# circuitPendulumLEDsSmall.net
KiCad netlist of a schematic drawn in EAGLE
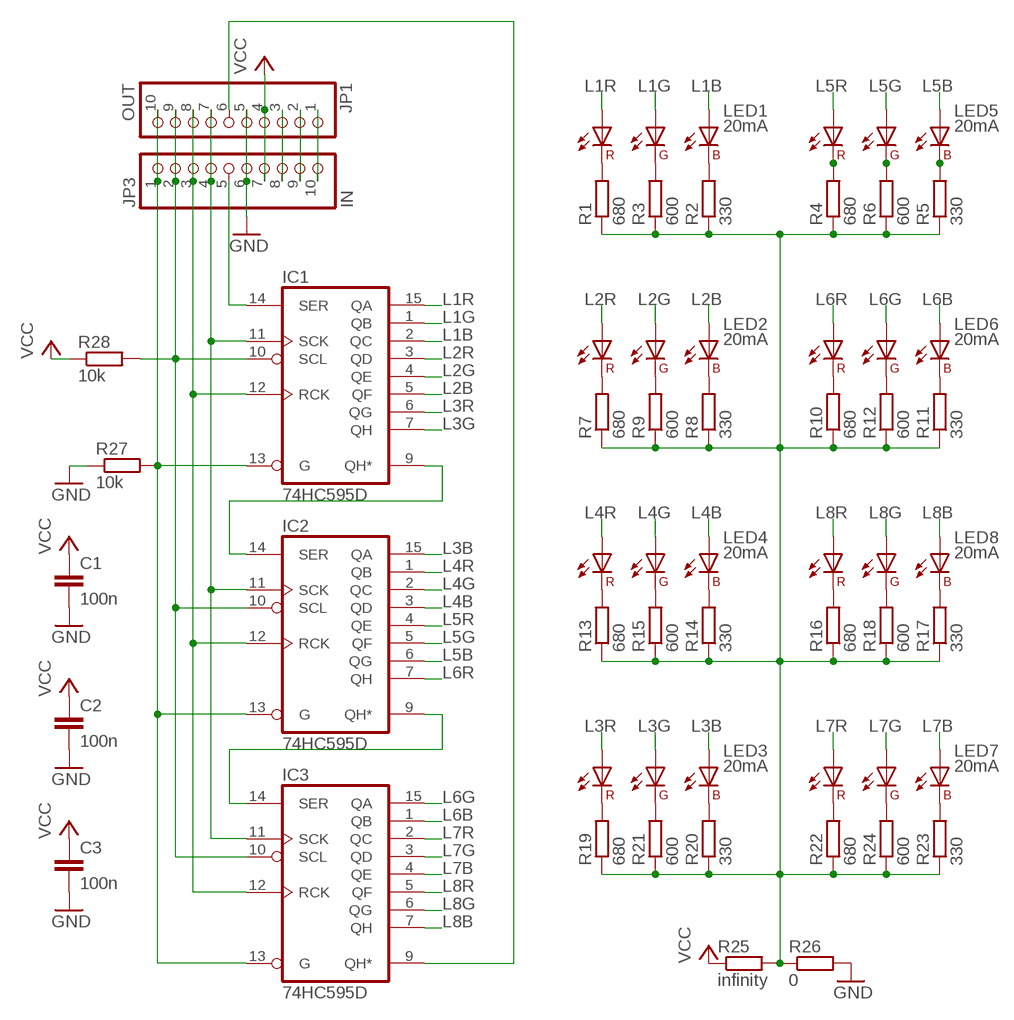
[diagram p0: schematic, sheet 1]

(export (version "E")
  (design (tool "Eeschema 10.0.6"))
  (components
    (comp (ref "C1")
      (value "100n")
      (footprint "eagle-import:C0603")
      (libsource (lib "eagle-import") (part "C-EUC0603"))
    )
    (comp (ref "C2")
      (value "100n")
      (footprint "eagle-import:C0603")
      (libsource (lib "eagle-import") (part "C-EUC0603"))
    )
    (comp (ref "C3")
      (value "100n")
      (footprint "eagle-import:C0603")
      (libsource (lib "eagle-import") (part "C-EUC0603"))
    )
    (comp (ref "IC1")
      (value "74HC595D")
      (footprint "eagle-import:SO16")
      (libsource (lib "eagle-import") (part "74595DHC"))
    )
    (comp (ref "IC2")
      (value "74HC595D")
      (footprint "eagle-import:SO16")
      (libsource (lib "eagle-import") (part "74595DHC"))
    )
    (comp (ref "IC3")
      (value "74HC595D")
      (footprint "eagle-import:SO16")
      (libsource (lib "eagle-import") (part "74595DHC"))
    )
    (comp (ref "JP1")
      (value "OUT")
      (footprint "eagle-import:1X10SMD_90")
      (libsource (lib "eagle-import") (part "PINHD-1X10_2.54-SMD-90°"))
    )
    (comp (ref "JP3")
      (value "IN")
      (footprint "eagle-import:1X10SMD_90")
      (libsource (lib "eagle-import") (part "PINHD-1X10_2.54-SMD-90°"))
    )
    (comp (ref "LED1")
      (value "20mA")
      (footprint "eagle-import:PLCC-6_SAMSUNG")
      (libsource (lib "eagle-import") (part "PLCC-6-RGB-SAMSUNG"))
    )
    (comp (ref "LED2")
      (value "20mA")
      (footprint "eagle-import:PLCC-6_SAMSUNG")
      (libsource (lib "eagle-import") (part "PLCC-6-RGB-SAMSUNG"))
    )
    (comp (ref "LED3")
      (value "20mA")
      (footprint "eagle-import:PLCC-6_SAMSUNG")
      (libsource (lib "eagle-import") (part "PLCC-6-RGB-SAMSUNG"))
    )
    (comp (ref "LED4")
      (value "20mA")
      (footprint "eagle-import:PLCC-6_SAMSUNG")
      (libsource (lib "eagle-import") (part "PLCC-6-RGB-SAMSUNG"))
    )
    (comp (ref "LED5")
      (value "20mA")
      (footprint "eagle-import:PLCC-6_SAMSUNG")
      (libsource (lib "eagle-import") (part "PLCC-6-RGB-SAMSUNG"))
    )
    (comp (ref "LED6")
      (value "20mA")
      (footprint "eagle-import:PLCC-6_SAMSUNG")
      (libsource (lib "eagle-import") (part "PLCC-6-RGB-SAMSUNG"))
    )
    (comp (ref "LED7")
      (value "20mA")
      (footprint "eagle-import:PLCC-6_SAMSUNG")
      (libsource (lib "eagle-import") (part "PLCC-6-RGB-SAMSUNG"))
    )
    (comp (ref "LED8")
      (value "20mA")
      (footprint "eagle-import:PLCC-6_SAMSUNG")
      (libsource (lib "eagle-import") (part "PLCC-6-RGB-SAMSUNG"))
    )
    (comp (ref "R1")
      (value "680")
      (footprint "eagle-import:R0603")
      (libsource (lib "eagle-import") (part "R-EU_R0603"))
    )
    (comp (ref "R2")
      (value "330")
      (footprint "eagle-import:R0603")
      (libsource (lib "eagle-import") (part "R-EU_R0603"))
    )
    (comp (ref "R3")
      (value "600")
      (footprint "eagle-import:R0603")
      (libsource (lib "eagle-import") (part "R-EU_R0603"))
    )
    (comp (ref "R4")
      (value "680")
      (footprint "eagle-import:R0603")
      (libsource (lib "eagle-import") (part "R-EU_R0603"))
    )
    (comp (ref "R5")
      (value "330")
      (footprint "eagle-import:R0603")
      (libsource (lib "eagle-import") (part "R-EU_R0603"))
    )
    (comp (ref "R6")
      (value "600")
      (footprint "eagle-import:R0603")
      (libsource (lib "eagle-import") (part "R-EU_R0603"))
    )
    (comp (ref "R7")
      (value "680")
      (footprint "eagle-import:R0603")
      (libsource (lib "eagle-import") (part "R-EU_R0603"))
    )
    (comp (ref "R8")
      (value "330")
      (footprint "eagle-import:R0603")
      (libsource (lib "eagle-import") (part "R-EU_R0603"))
    )
    (comp (ref "R9")
      (value "600")
      (footprint "eagle-import:R0603")
      (libsource (lib "eagle-import") (part "R-EU_R0603"))
    )
    (comp (ref "R10")
      (value "680")
      (footprint "eagle-import:R0603")
      (libsource (lib "eagle-import") (part "R-EU_R0603"))
    )
    (comp (ref "R11")
      (value "330")
      (footprint "eagle-import:R0603")
      (libsource (lib "eagle-import") (part "R-EU_R0603"))
    )
    (comp (ref "R12")
      (value "600")
      (footprint "eagle-import:R0603")
      (libsource (lib "eagle-import") (part "R-EU_R0603"))
    )
    (comp (ref "R13")
      (value "680")
      (footprint "eagle-import:R0603")
      (libsource (lib "eagle-import") (part "R-EU_R0603"))
    )
    (comp (ref "R14")
      (value "330")
      (footprint "eagle-import:R0603")
      (libsource (lib "eagle-import") (part "R-EU_R0603"))
    )
    (comp (ref "R15")
      (value "600")
      (footprint "eagle-import:R0603")
      (libsource (lib "eagle-import") (part "R-EU_R0603"))
    )
    (comp (ref "R16")
      (value "680")
      (footprint "eagle-import:R0603")
      (libsource (lib "eagle-import") (part "R-EU_R0603"))
    )
    (comp (ref "R17")
      (value "330")
      (footprint "eagle-import:R0603")
      (libsource (lib "eagle-import") (part "R-EU_R0603"))
    )
    (comp (ref "R18")
      (value "600")
      (footprint "eagle-import:R0603")
      (libsource (lib "eagle-import") (part "R-EU_R0603"))
    )
    (comp (ref "R19")
      (value "680")
      (footprint "eagle-import:R0603")
      (libsource (lib "eagle-import") (part "R-EU_R0603"))
    )
    (comp (ref "R20")
      (value "330")
      (footprint "eagle-import:R0603")
      (libsource (lib "eagle-import") (part "R-EU_R0603"))
    )
    (comp (ref "R21")
      (value "600")
      (footprint "eagle-import:R0603")
      (libsource (lib "eagle-import") (part "R-EU_R0603"))
    )
    (comp (ref "R22")
      (value "680")
      (footprint "eagle-import:R0603")
      (libsource (lib "eagle-import") (part "R-EU_R0603"))
    )
    (comp (ref "R23")
      (value "330")
      (footprint "eagle-import:R0603")
      (libsource (lib "eagle-import") (part "R-EU_R0603"))
    )
    (comp (ref "R24")
      (value "600")
      (footprint "eagle-import:R0603")
      (libsource (lib "eagle-import") (part "R-EU_R0603"))
    )
    (comp (ref "R25")
      (value "infinity")
      (footprint "eagle-import:R0603")
      (libsource (lib "eagle-import") (part "R-EU_R0603"))
    )
    (comp (ref "R26")
      (value "0")
      (footprint "eagle-import:R0603")
      (libsource (lib "eagle-import") (part "R-EU_R0603"))
    )
    (comp (ref "R27")
      (value "10k")
      (footprint "eagle-import:R0603")
      (libsource (lib "eagle-import") (part "R-EU_R0603"))
    )
    (comp (ref "R28")
      (value "10k")
      (footprint "eagle-import:R0603")
      (libsource (lib "eagle-import") (part "R-EU_R0603"))
    )
  )
  (nets
    (net (code "1") (name "/L1B") (class "Default")
      (node (ref "IC1") (pin "2") (pinfunction "QC_2") (pintype "tri_state"))
      (node (ref "LED1") (pin "3") (pinfunction "AB_3") (pintype "passive"))
    )
    (net (code "2") (name "/L1G") (class "Default")
      (node (ref "IC1") (pin "1") (pinfunction "QB_1") (pintype "tri_state"))
      (node (ref "LED1") (pin "2") (pinfunction "AG_2") (pintype "passive"))
    )
    (net (code "3") (name "/L1R") (class "Default")
      (node (ref "IC1") (pin "15") (pinfunction "QA_15") (pintype "tri_state"))
      (node (ref "LED1") (pin "1") (pinfunction "AR_1") (pintype "passive"))
    )
    (net (code "4") (name "/L2B") (class "Default")
      (node (ref "IC1") (pin "5") (pinfunction "QF_5") (pintype "tri_state"))
      (node (ref "LED2") (pin "3") (pinfunction "AB_3") (pintype "passive"))
    )
    (net (code "5") (name "/L2G") (class "Default")
      (node (ref "IC1") (pin "4") (pinfunction "QE_4") (pintype "tri_state"))
      (node (ref "LED2") (pin "2") (pinfunction "AG_2") (pintype "passive"))
    )
    (net (code "6") (name "/L2R") (class "Default")
      (node (ref "IC1") (pin "3") (pinfunction "QD_3") (pintype "tri_state"))
      (node (ref "LED2") (pin "1") (pinfunction "AR_1") (pintype "passive"))
    )
    (net (code "7") (name "/L3B") (class "Default")
      (node (ref "IC2") (pin "15") (pinfunction "QA_15") (pintype "tri_state"))
      (node (ref "LED3") (pin "3") (pinfunction "AB_3") (pintype "passive"))
    )
    (net (code "8") (name "/L3G") (class "Default")
      (node (ref "IC1") (pin "7") (pinfunction "QH_7") (pintype "tri_state"))
      (node (ref "LED3") (pin "2") (pinfunction "AG_2") (pintype "passive"))
    )
    (net (code "9") (name "/L3R") (class "Default")
      (node (ref "IC1") (pin "6") (pinfunction "QG_6") (pintype "tri_state"))
      (node (ref "LED3") (pin "1") (pinfunction "AR_1") (pintype "passive"))
    )
    (net (code "10") (name "/L4B") (class "Default")
      (node (ref "IC2") (pin "3") (pinfunction "QD_3") (pintype "tri_state"))
      (node (ref "LED4") (pin "3") (pinfunction "AB_3") (pintype "passive"))
    )
    (net (code "11") (name "/L4G") (class "Default")
      (node (ref "IC2") (pin "2") (pinfunction "QC_2") (pintype "tri_state"))
      (node (ref "LED4") (pin "2") (pinfunction "AG_2") (pintype "passive"))
    )
    (net (code "12") (name "/L4R") (class "Default")
      (node (ref "IC2") (pin "1") (pinfunction "QB_1") (pintype "tri_state"))
      (node (ref "LED4") (pin "1") (pinfunction "AR_1") (pintype "passive"))
    )
    (net (code "13") (name "/L5B") (class "Default")
      (node (ref "IC2") (pin "6") (pinfunction "QG_6") (pintype "tri_state"))
      (node (ref "LED5") (pin "3") (pinfunction "AB_3") (pintype "passive"))
    )
    (net (code "14") (name "/L5G") (class "Default")
      (node (ref "IC2") (pin "5") (pinfunction "QF_5") (pintype "tri_state"))
      (node (ref "LED5") (pin "2") (pinfunction "AG_2") (pintype "passive"))
    )
    (net (code "15") (name "/L5R") (class "Default")
      (node (ref "IC2") (pin "4") (pinfunction "QE_4") (pintype "tri_state"))
      (node (ref "LED5") (pin "1") (pinfunction "AR_1") (pintype "passive"))
    )
    (net (code "16") (name "/L6B") (class "Default")
      (node (ref "IC3") (pin "1") (pinfunction "QB_1") (pintype "tri_state"))
      (node (ref "LED6") (pin "3") (pinfunction "AB_3") (pintype "passive"))
    )
    (net (code "17") (name "/L6G") (class "Default")
      (node (ref "IC3") (pin "15") (pinfunction "QA_15") (pintype "tri_state"))
      (node (ref "LED6") (pin "2") (pinfunction "AG_2") (pintype "passive"))
    )
    (net (code "18") (name "/L6R") (class "Default")
      (node (ref "IC2") (pin "7") (pinfunction "QH_7") (pintype "tri_state"))
      (node (ref "LED6") (pin "1") (pinfunction "AR_1") (pintype "passive"))
    )
    (net (code "19") (name "/L7B") (class "Default")
      (node (ref "IC3") (pin "4") (pinfunction "QE_4") (pintype "tri_state"))
      (node (ref "LED7") (pin "3") (pinfunction "AB_3") (pintype "passive"))
    )
    (net (code "20") (name "/L7G") (class "Default")
      (node (ref "IC3") (pin "3") (pinfunction "QD_3") (pintype "tri_state"))
      (node (ref "LED7") (pin "2") (pinfunction "AG_2") (pintype "passive"))
    )
    (net (code "21") (name "/L7R") (class "Default")
      (node (ref "IC3") (pin "2") (pinfunction "QC_2") (pintype "tri_state"))
      (node (ref "LED7") (pin "1") (pinfunction "AR_1") (pintype "passive"))
    )
    (net (code "22") (name "/L8B") (class "Default")
      (node (ref "IC3") (pin "7") (pinfunction "QH_7") (pintype "tri_state"))
      (node (ref "LED8") (pin "3") (pinfunction "AB_3") (pintype "passive"))
    )
    (net (code "23") (name "/L8G") (class "Default")
      (node (ref "IC3") (pin "6") (pinfunction "QG_6") (pintype "tri_state"))
      (node (ref "LED8") (pin "2") (pinfunction "AG_2") (pintype "passive"))
    )
    (net (code "24") (name "/L8R") (class "Default")
      (node (ref "IC3") (pin "5") (pinfunction "QF_5") (pintype "tri_state"))
      (node (ref "LED8") (pin "1") (pinfunction "AR_1") (pintype "passive"))
    )
    (net (code "25") (name "GND") (class "Default")
      (node (ref "C1") (pin "2") (pinfunction "2_2") (pintype "passive"))
      (node (ref "C2") (pin "2") (pinfunction "2_2") (pintype "passive"))
      (node (ref "C3") (pin "2") (pinfunction "2_2") (pintype "passive"))
      (node (ref "JP1") (pin "5") (pinfunction "5_5") (pintype "passive"))
      (node (ref "JP3") (pin "6") (pinfunction "6_6") (pintype "passive"))
      (node (ref "R26") (pin "2") (pinfunction "2_2") (pintype "passive"))
      (node (ref "R27") (pin "1") (pinfunction "1_1") (pintype "passive"))
    )
    (net (code "26") (name "Net-(IC1A-G)") (class "Default")
      (node (ref "IC1") (pin "13") (pinfunction "G_13") (pintype "input"))
      (node (ref "IC2") (pin "13") (pinfunction "G_13") (pintype "input"))
      (node (ref "IC3") (pin "13") (pinfunction "G_13") (pintype "input"))
      (node (ref "JP1") (pin "10") (pinfunction "10_10") (pintype "passive"))
      (node (ref "JP3") (pin "1") (pinfunction "1_1") (pintype "passive"))
      (node (ref "R27") (pin "2") (pinfunction "2_2") (pintype "passive"))
    )
    (net (code "27") (name "Net-(IC1A-QH*)") (class "Default")
      (node (ref "IC1") (pin "9") (pinfunction "QH*_9") (pintype "tri_state"))
      (node (ref "IC2") (pin "14") (pinfunction "SER_14") (pintype "input"))
    )
    (net (code "28") (name "Net-(IC1A-RCK)") (class "Default")
      (node (ref "IC1") (pin "12") (pinfunction "RCK_12") (pintype "input"))
      (node (ref "IC2") (pin "12") (pinfunction "RCK_12") (pintype "input"))
      (node (ref "IC3") (pin "12") (pinfunction "RCK_12") (pintype "input"))
      (node (ref "JP1") (pin "8") (pinfunction "8_8") (pintype "passive"))
      (node (ref "JP3") (pin "3") (pinfunction "3_3") (pintype "passive"))
    )
    (net (code "29") (name "Net-(IC1A-SCK)") (class "Default")
      (node (ref "IC1") (pin "11") (pinfunction "SCK_11") (pintype "input"))
      (node (ref "IC2") (pin "11") (pinfunction "SCK_11") (pintype "input"))
      (node (ref "IC3") (pin "11") (pinfunction "SCK_11") (pintype "input"))
      (node (ref "JP1") (pin "7") (pinfunction "7_7") (pintype "passive"))
      (node (ref "JP3") (pin "4") (pinfunction "4_4") (pintype "passive"))
    )
    (net (code "30") (name "Net-(IC1A-SCL)") (class "Default")
      (node (ref "IC1") (pin "10") (pinfunction "SCL_10") (pintype "input"))
      (node (ref "IC2") (pin "10") (pinfunction "SCL_10") (pintype "input"))
      (node (ref "IC3") (pin "10") (pinfunction "SCL_10") (pintype "input"))
      (node (ref "JP1") (pin "9") (pinfunction "9_9") (pintype "passive"))
      (node (ref "JP3") (pin "2") (pinfunction "2_2") (pintype "passive"))
      (node (ref "R28") (pin "2") (pinfunction "2_2") (pintype "passive"))
    )
    (net (code "31") (name "Net-(IC1A-SER)") (class "Default")
      (node (ref "IC1") (pin "14") (pinfunction "SER_14") (pintype "input"))
      (node (ref "JP3") (pin "5") (pinfunction "5_5") (pintype "passive"))
    )
    (net (code "32") (name "Net-(IC2A-QH*)") (class "Default")
      (node (ref "IC2") (pin "9") (pinfunction "QH*_9") (pintype "tri_state"))
      (node (ref "IC3") (pin "14") (pinfunction "SER_14") (pintype "input"))
    )
    (net (code "33") (name "Net-(IC3A-QH*)") (class "Default")
      (node (ref "IC3") (pin "9") (pinfunction "QH*_9") (pintype "tri_state"))
      (node (ref "JP1") (pin "6") (pinfunction "6_6") (pintype "passive"))
    )
    (net (code "34") (name "Net-(JP1-Pad1)") (class "Default")
      (node (ref "JP1") (pin "1") (pinfunction "1_1") (pintype "passive"))
      (node (ref "JP3") (pin "10") (pinfunction "10_10") (pintype "passive"))
    )
    (net (code "35") (name "Net-(JP1-Pad2)") (class "Default")
      (node (ref "JP1") (pin "2") (pinfunction "2_2") (pintype "passive"))
      (node (ref "JP3") (pin "9") (pinfunction "9_9") (pintype "passive"))
    )
    (net (code "36") (name "Net-(JP1-Pad3)") (class "Default")
      (node (ref "JP1") (pin "3") (pinfunction "3_3") (pintype "passive"))
      (node (ref "JP3") (pin "8") (pinfunction "8_8") (pintype "passive"))
    )
    (net (code "37") (name "Net-(LED1-CB)") (class "Default")
      (node (ref "LED1") (pin "6") (pinfunction "CB_6") (pintype "passive"))
      (node (ref "R2") (pin "2") (pinfunction "2_2") (pintype "passive"))
    )
    (net (code "38") (name "Net-(LED1-CG)") (class "Default")
      (node (ref "LED1") (pin "5") (pinfunction "CG_5") (pintype "passive"))
      (node (ref "R3") (pin "2") (pinfunction "2_2") (pintype "passive"))
    )
    (net (code "39") (name "Net-(LED1-CR)") (class "Default")
      (node (ref "LED1") (pin "4") (pinfunction "CR_4") (pintype "passive"))
      (node (ref "R1") (pin "2") (pinfunction "2_2") (pintype "passive"))
    )
    (net (code "40") (name "Net-(LED2-CB)") (class "Default")
      (node (ref "LED2") (pin "6") (pinfunction "CB_6") (pintype "passive"))
      (node (ref "R8") (pin "2") (pinfunction "2_2") (pintype "passive"))
    )
    (net (code "41") (name "Net-(LED2-CG)") (class "Default")
      (node (ref "LED2") (pin "5") (pinfunction "CG_5") (pintype "passive"))
      (node (ref "R9") (pin "2") (pinfunction "2_2") (pintype "passive"))
    )
    (net (code "42") (name "Net-(LED2-CR)") (class "Default")
      (node (ref "LED2") (pin "4") (pinfunction "CR_4") (pintype "passive"))
      (node (ref "R7") (pin "2") (pinfunction "2_2") (pintype "passive"))
    )
    (net (code "43") (name "Net-(LED3-CB)") (class "Default")
      (node (ref "LED3") (pin "6") (pinfunction "CB_6") (pintype "passive"))
      (node (ref "R20") (pin "2") (pinfunction "2_2") (pintype "passive"))
    )
    (net (code "44") (name "Net-(LED3-CG)") (class "Default")
      (node (ref "LED3") (pin "5") (pinfunction "CG_5") (pintype "passive"))
      (node (ref "R21") (pin "2") (pinfunction "2_2") (pintype "passive"))
    )
    (net (code "45") (name "Net-(LED3-CR)") (class "Default")
      (node (ref "LED3") (pin "4") (pinfunction "CR_4") (pintype "passive"))
      (node (ref "R19") (pin "2") (pinfunction "2_2") (pintype "passive"))
    )
    (net (code "46") (name "Net-(LED4-CB)") (class "Default")
      (node (ref "LED4") (pin "6") (pinfunction "CB_6") (pintype "passive"))
      (node (ref "R14") (pin "2") (pinfunction "2_2") (pintype "passive"))
    )
    (net (code "47") (name "Net-(LED4-CG)") (class "Default")
      (node (ref "LED4") (pin "5") (pinfunction "CG_5") (pintype "passive"))
      (node (ref "R15") (pin "2") (pinfunction "2_2") (pintype "passive"))
    )
    (net (code "48") (name "Net-(LED4-CR)") (class "Default")
      (node (ref "LED4") (pin "4") (pinfunction "CR_4") (pintype "passive"))
      (node (ref "R13") (pin "2") (pinfunction "2_2") (pintype "passive"))
    )
    (net (code "49") (name "Net-(LED5-CB)") (class "Default")
      (node (ref "LED5") (pin "6") (pinfunction "CB_6") (pintype "passive"))
      (node (ref "R5") (pin "2") (pinfunction "2_2") (pintype "passive"))
    )
    (net (code "50") (name "Net-(LED5-CG)") (class "Default")
      (node (ref "LED5") (pin "5") (pinfunction "CG_5") (pintype "passive"))
      (node (ref "R6") (pin "2") (pinfunction "2_2") (pintype "passive"))
    )
    (net (code "51") (name "Net-(LED5-CR)") (class "Default")
      (node (ref "LED5") (pin "4") (pinfunction "CR_4") (pintype "passive"))
      (node (ref "R4") (pin "2") (pinfunction "2_2") (pintype "passive"))
    )
    (net (code "52") (name "Net-(LED6-CB)") (class "Default")
      (node (ref "LED6") (pin "6") (pinfunction "CB_6") (pintype "passive"))
      (node (ref "R11") (pin "2") (pinfunction "2_2") (pintype "passive"))
    )
    (net (code "53") (name "Net-(LED6-CG)") (class "Default")
      (node (ref "LED6") (pin "5") (pinfunction "CG_5") (pintype "passive"))
      (node (ref "R12") (pin "2") (pinfunction "2_2") (pintype "passive"))
    )
    (net (code "54") (name "Net-(LED6-CR)") (class "Default")
      (node (ref "LED6") (pin "4") (pinfunction "CR_4") (pintype "passive"))
      (node (ref "R10") (pin "2") (pinfunction "2_2") (pintype "passive"))
    )
    (net (code "55") (name "Net-(LED7-CB)") (class "Default")
      (node (ref "LED7") (pin "6") (pinfunction "CB_6") (pintype "passive"))
      (node (ref "R23") (pin "2") (pinfunction "2_2") (pintype "passive"))
    )
    (net (code "56") (name "Net-(LED7-CG)") (class "Default")
      (node (ref "LED7") (pin "5") (pinfunction "CG_5") (pintype "passive"))
      (node (ref "R24") (pin "2") (pinfunction "2_2") (pintype "passive"))
    )
    (net (code "57") (name "Net-(LED7-CR)") (class "Default")
      (node (ref "LED7") (pin "4") (pinfunction "CR_4") (pintype "passive"))
      (node (ref "R22") (pin "2") (pinfunction "2_2") (pintype "passive"))
    )
    (net (code "58") (name "Net-(LED8-CB)") (class "Default")
      (node (ref "LED8") (pin "6") (pinfunction "CB_6") (pintype "passive"))
      (node (ref "R17") (pin "2") (pinfunction "2_2") (pintype "passive"))
    )
    (net (code "59") (name "Net-(LED8-CG)") (class "Default")
      (node (ref "LED8") (pin "5") (pinfunction "CG_5") (pintype "passive"))
      (node (ref "R18") (pin "2") (pinfunction "2_2") (pintype "passive"))
    )
    (net (code "60") (name "Net-(LED8-CR)") (class "Default")
      (node (ref "LED8") (pin "4") (pinfunction "CR_4") (pintype "passive"))
      (node (ref "R16") (pin "2") (pinfunction "2_2") (pintype "passive"))
    )
    (net (code "61") (name "Net-(R1-Pad1)") (class "Default")
      (node (ref "R1") (pin "1") (pinfunction "1_1") (pintype "passive"))
      (node (ref "R10") (pin "1") (pinfunction "1_1") (pintype "passive"))
      (node (ref "R11") (pin "1") (pinfunction "1_1") (pintype "passive"))
      (node (ref "R12") (pin "1") (pinfunction "1_1") (pintype "passive"))
      (node (ref "R13") (pin "1") (pinfunction "1_1") (pintype "passive"))
      (node (ref "R14") (pin "1") (pinfunction "1_1") (pintype "passive"))
      (node (ref "R15") (pin "1") (pinfunction "1_1") (pintype "passive"))
      (node (ref "R16") (pin "1") (pinfunction "1_1") (pintype "passive"))
      (node (ref "R17") (pin "1") (pinfunction "1_1") (pintype "passive"))
      (node (ref "R18") (pin "1") (pinfunction "1_1") (pintype "passive"))
      (node (ref "R19") (pin "1") (pinfunction "1_1") (pintype "passive"))
      (node (ref "R2") (pin "1") (pinfunction "1_1") (pintype "passive"))
      (node (ref "R20") (pin "1") (pinfunction "1_1") (pintype "passive"))
      (node (ref "R21") (pin "1") (pinfunction "1_1") (pintype "passive"))
      (node (ref "R22") (pin "1") (pinfunction "1_1") (pintype "passive"))
      (node (ref "R23") (pin "1") (pinfunction "1_1") (pintype "passive"))
      (node (ref "R24") (pin "1") (pinfunction "1_1") (pintype "passive"))
      (node (ref "R25") (pin "2") (pinfunction "2_2") (pintype "passive"))
      (node (ref "R26") (pin "1") (pinfunction "1_1") (pintype "passive"))
      (node (ref "R3") (pin "1") (pinfunction "1_1") (pintype "passive"))
      (node (ref "R4") (pin "1") (pinfunction "1_1") (pintype "passive"))
      (node (ref "R5") (pin "1") (pinfunction "1_1") (pintype "passive"))
      (node (ref "R6") (pin "1") (pinfunction "1_1") (pintype "passive"))
      (node (ref "R7") (pin "1") (pinfunction "1_1") (pintype "passive"))
      (node (ref "R8") (pin "1") (pinfunction "1_1") (pintype "passive"))
      (node (ref "R9") (pin "1") (pinfunction "1_1") (pintype "passive"))
    )
    (net (code "62") (name "VCC") (class "Default")
      (node (ref "C1") (pin "1") (pinfunction "1_1") (pintype "passive"))
      (node (ref "C2") (pin "1") (pinfunction "1_1") (pintype "passive"))
      (node (ref "C3") (pin "1") (pinfunction "1_1") (pintype "passive"))
      (node (ref "JP1") (pin "4") (pinfunction "4_4") (pintype "passive"))
      (node (ref "JP3") (pin "7") (pinfunction "7_7") (pintype "passive"))
      (node (ref "R25") (pin "1") (pinfunction "1_1") (pintype "passive"))
      (node (ref "R28") (pin "1") (pinfunction "1_1") (pintype "passive"))
    )
  )
)
